# 1.net
KiCad netlist of a schematic drawn in Altium Designer
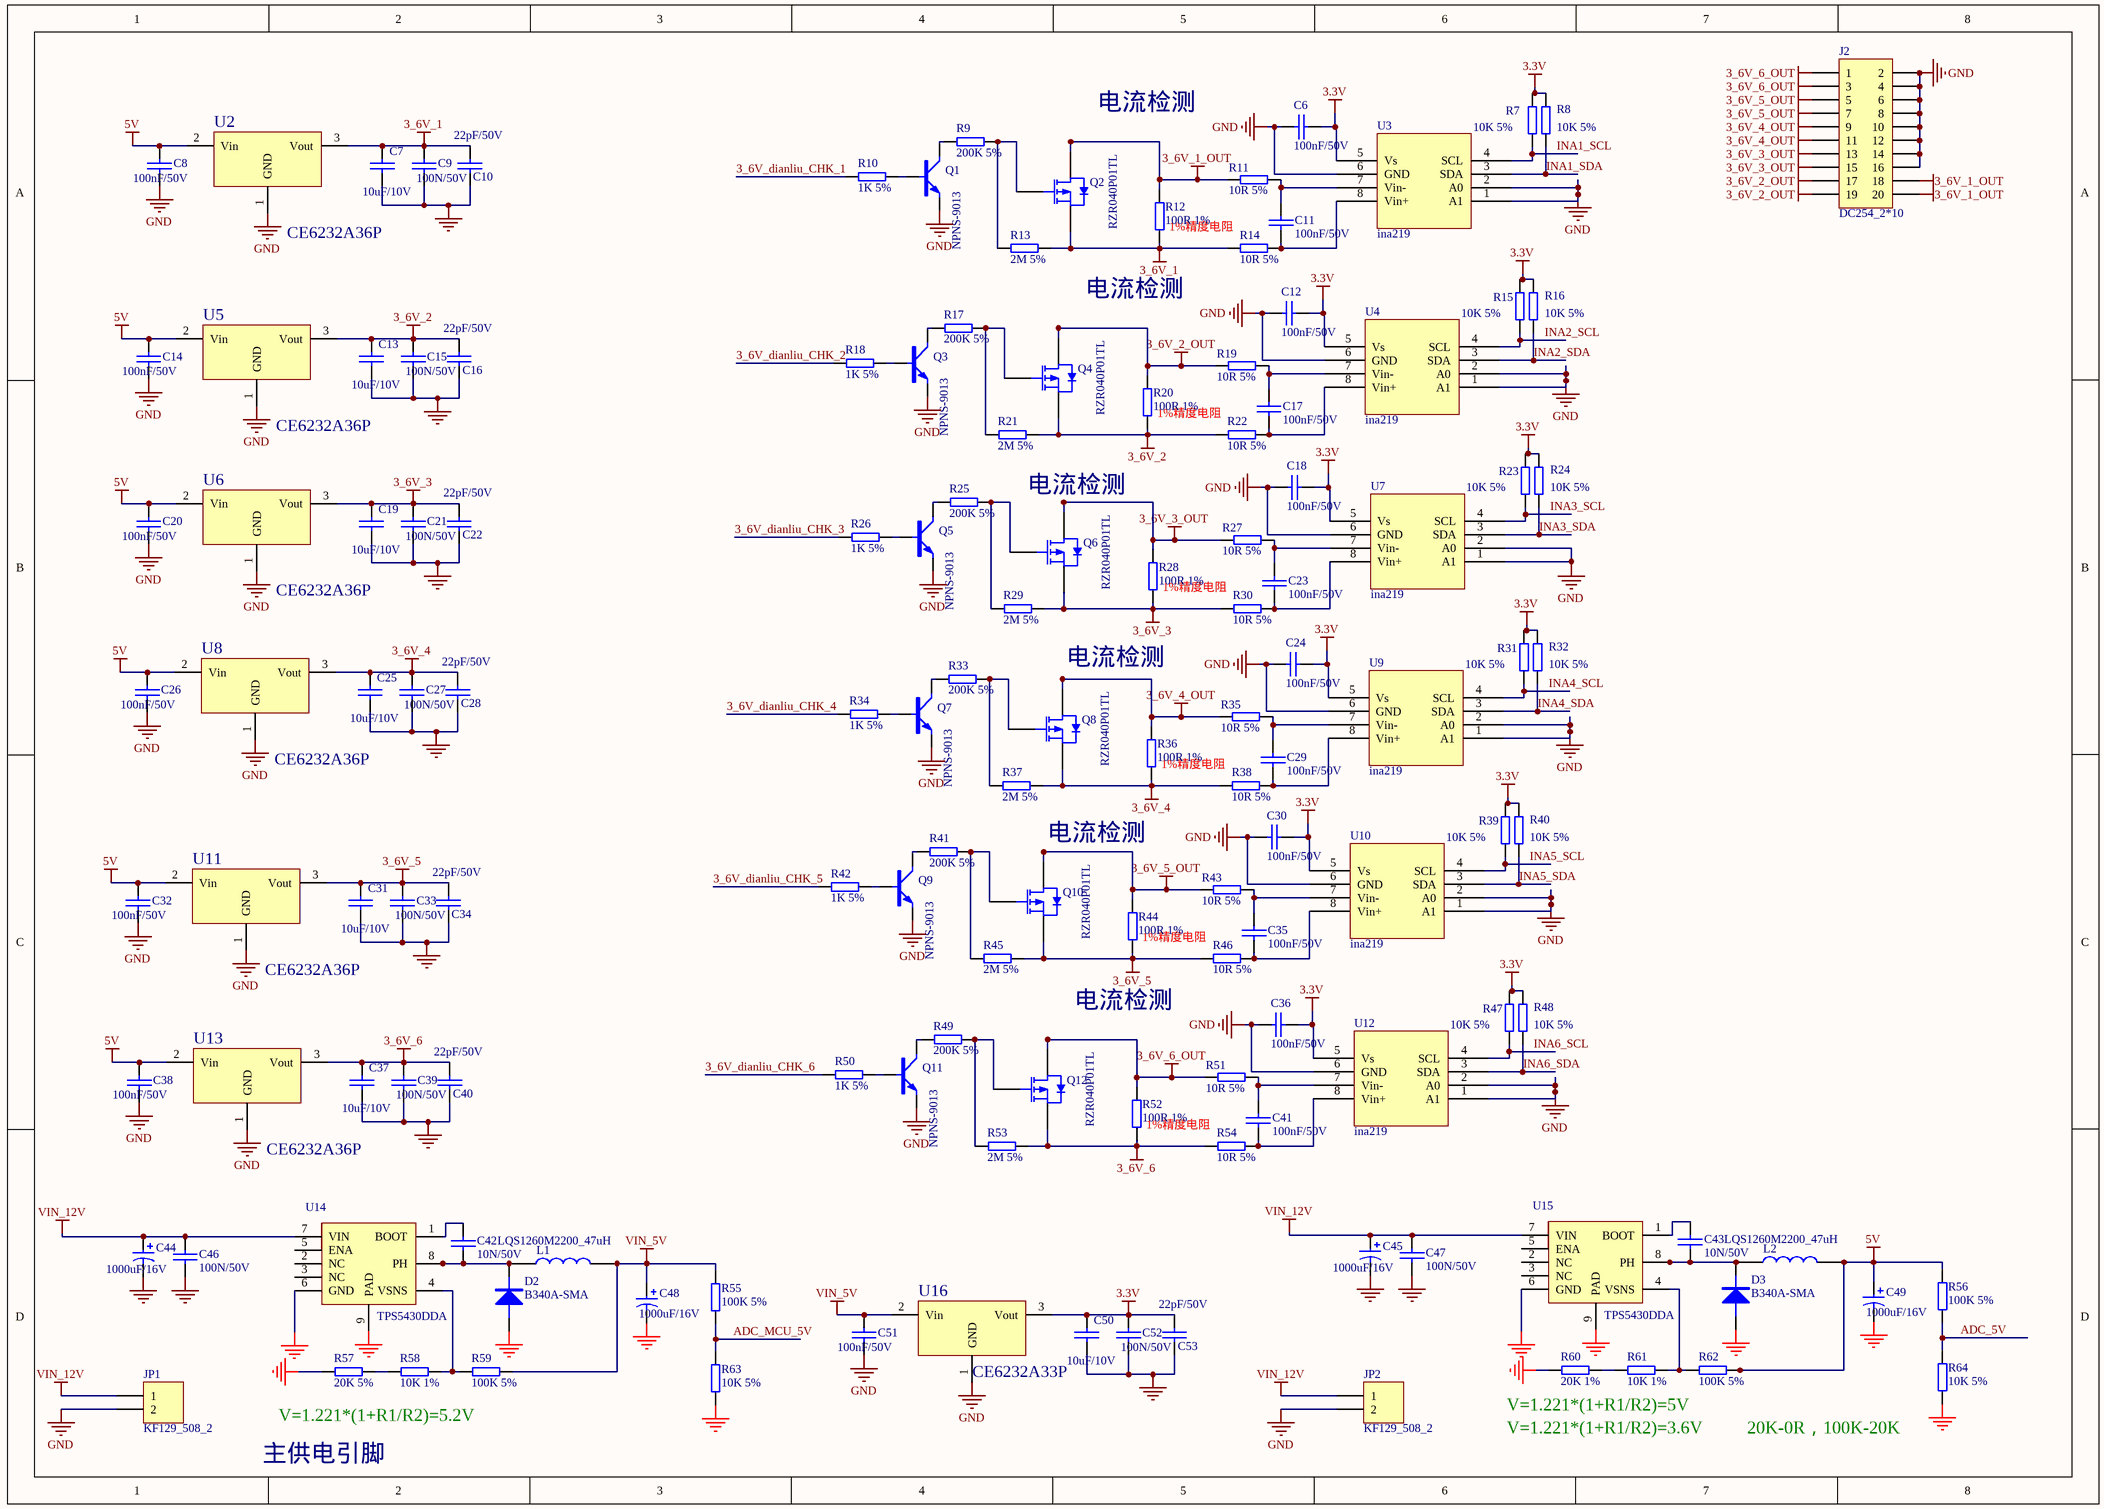
[diagram p0: 功耗测试工装原理图1.SchDoc]

(export (version "E")
  (design (tool "Eeschema 10.0.6"))
  (components
    (comp (ref "C6")
      (value "100nF/50V")
      (footprint "CAP0603")
      (description "104pF,50 V,±10%,0603,国巨,CC0603KRX7R9BB104")
      (fields (field (name "PART NUMBER") "101020103-0021"))
      (libsource (lib "Database_Libs2") (part "CC03K7R9_100N"))
    )
    (comp (ref "C7")
      (value "10uF/10V")
      (footprint "CAP0603")
      (description "106pF,10 V,±10%,0603,村田,GRM188R61A106KE47D")
      (fields (field (name "PART NUMBER") "101020103-0026"))
      (libsource (lib "Database_Libs2") (part "CC03K5R6_10U"))
    )
    (comp (ref "C8")
      (value "100nF/50V")
      (footprint "CAP0603")
      (description "104pF,50 V,±10%,0603,国巨,CC0603KRX7R9BB104")
      (fields (field (name "PART NUMBER") "101020103-0021"))
      (libsource (lib "Database_Libs2") (part "CC03K7R9_100N"))
    )
    (comp (ref "C9")
      (value "100N/50V")
      (footprint "CAP0603")
      (description "100N/50V，±10%，0603")
      (fields (field (name "PART NUMBER") "101020103-0021"))
      (libsource (lib "Database_Libs2") (part "CC03K7R9B_100N"))
    )
    (comp (ref "C10")
      (value "22pF/50V")
      (footprint "CAP0603")
      (description "22pF,50 V,±5%,0603,国巨,CC0603JRNPO9BN22")
      (fields (field (name "PART NUMBER") "101020103-0009"))
      (libsource (lib "Database_Libs2") (part "CC03JPO9_22P"))
    )
    (comp (ref "C11")
      (value "100nF/50V")
      (footprint "CAP0603")
      (description "104pF,50 V,±10%,0603,国巨,CC0603KRX7R9BB104")
      (fields (field (name "PART NUMBER") "101020103-0021"))
      (libsource (lib "Database_Libs2") (part "CC03K7R9_100N"))
    )
    (comp (ref "C12")
      (value "100nF/50V")
      (footprint "CAP0603")
      (description "104pF,50 V,±10%,0603,国巨,CC0603KRX7R9BB104")
      (fields (field (name "PART NUMBER") "101020103-0021"))
      (libsource (lib "Database_Libs2") (part "CC03K7R9_100N"))
    )
    (comp (ref "C13")
      (value "10uF/10V")
      (footprint "CAP0603")
      (description "106pF,10 V,±10%,0603,村田,GRM188R61A106KE47D")
      (fields (field (name "PART NUMBER") "101020103-0026"))
      (libsource (lib "Database_Libs2") (part "CC03K5R6_10U"))
    )
    (comp (ref "C14")
      (value "100nF/50V")
      (footprint "CAP0603")
      (description "104pF,50 V,±10%,0603,国巨,CC0603KRX7R9BB104")
      (fields (field (name "PART NUMBER") "101020103-0021"))
      (libsource (lib "Database_Libs2") (part "CC03K7R9_100N"))
    )
    (comp (ref "C15")
      (value "100N/50V")
      (footprint "CAP0603")
      (description "100N/50V，±10%，0603")
      (fields (field (name "PART NUMBER") "101020103-0021"))
      (libsource (lib "Database_Libs2") (part "CC03K7R9B_100N"))
    )
    (comp (ref "C16")
      (value "22pF/50V")
      (footprint "CAP0603")
      (description "22pF,50 V,±5%,0603,国巨,CC0603JRNPO9BN22")
      (fields (field (name "PART NUMBER") "101020103-0009"))
      (libsource (lib "Database_Libs2") (part "CC03JPO9_22P"))
    )
    (comp (ref "C17")
      (value "100nF/50V")
      (footprint "CAP0603")
      (description "104pF,50 V,±10%,0603,国巨,CC0603KRX7R9BB104")
      (fields (field (name "PART NUMBER") "101020103-0021"))
      (libsource (lib "Database_Libs2") (part "CC03K7R9_100N"))
    )
    (comp (ref "C18")
      (value "100nF/50V")
      (footprint "CAP0603")
      (description "104pF,50 V,±10%,0603,国巨,CC0603KRX7R9BB104")
      (fields (field (name "PART NUMBER") "101020103-0021"))
      (libsource (lib "Database_Libs2") (part "CC03K7R9_100N"))
    )
    (comp (ref "C19")
      (value "10uF/10V")
      (footprint "CAP0603")
      (description "106pF,10 V,±10%,0603,村田,GRM188R61A106KE47D")
      (fields (field (name "PART NUMBER") "101020103-0026"))
      (libsource (lib "Database_Libs2") (part "CC03K5R6_10U"))
    )
    (comp (ref "C20")
      (value "100nF/50V")
      (footprint "CAP0603")
      (description "104pF,50 V,±10%,0603,国巨,CC0603KRX7R9BB104")
      (fields (field (name "PART NUMBER") "101020103-0021"))
      (libsource (lib "Database_Libs2") (part "CC03K7R9_100N"))
    )
    (comp (ref "C21")
      (value "100N/50V")
      (footprint "CAP0603")
      (description "100N/50V，±10%，0603")
      (fields (field (name "PART NUMBER") "101020103-0021"))
      (libsource (lib "Database_Libs2") (part "CC03K7R9B_100N"))
    )
    (comp (ref "C22")
      (value "22pF/50V")
      (footprint "CAP0603")
      (description "22pF,50 V,±5%,0603,国巨,CC0603JRNPO9BN22")
      (fields (field (name "PART NUMBER") "101020103-0009"))
      (libsource (lib "Database_Libs2") (part "CC03JPO9_22P"))
    )
    (comp (ref "C23")
      (value "100nF/50V")
      (footprint "CAP0603")
      (description "104pF,50 V,±10%,0603,国巨,CC0603KRX7R9BB104")
      (fields (field (name "PART NUMBER") "101020103-0021"))
      (libsource (lib "Database_Libs2") (part "CC03K7R9_100N"))
    )
    (comp (ref "C24")
      (value "100nF/50V")
      (footprint "CAP0603")
      (description "104pF,50 V,±10%,0603,国巨,CC0603KRX7R9BB104")
      (fields (field (name "PART NUMBER") "101020103-0021"))
      (libsource (lib "Database_Libs2") (part "CC03K7R9_100N"))
    )
    (comp (ref "C25")
      (value "10uF/10V")
      (footprint "CAP0603")
      (description "106pF,10 V,±10%,0603,村田,GRM188R61A106KE47D")
      (fields (field (name "PART NUMBER") "101020103-0026"))
      (libsource (lib "Database_Libs2") (part "CC03K5R6_10U"))
    )
    (comp (ref "C26")
      (value "100nF/50V")
      (footprint "CAP0603")
      (description "104pF,50 V,±10%,0603,国巨,CC0603KRX7R9BB104")
      (fields (field (name "PART NUMBER") "101020103-0021"))
      (libsource (lib "Database_Libs2") (part "CC03K7R9_100N"))
    )
    (comp (ref "C27")
      (value "100N/50V")
      (footprint "CAP0603")
      (description "100N/50V，±10%，0603")
      (fields (field (name "PART NUMBER") "101020103-0021"))
      (libsource (lib "Database_Libs2") (part "CC03K7R9B_100N"))
    )
    (comp (ref "C28")
      (value "22pF/50V")
      (footprint "CAP0603")
      (description "22pF,50 V,±5%,0603,国巨,CC0603JRNPO9BN22")
      (fields (field (name "PART NUMBER") "101020103-0009"))
      (libsource (lib "Database_Libs2") (part "CC03JPO9_22P"))
    )
    (comp (ref "C29")
      (value "100nF/50V")
      (footprint "CAP0603")
      (description "104pF,50 V,±10%,0603,国巨,CC0603KRX7R9BB104")
      (fields (field (name "PART NUMBER") "101020103-0021"))
      (libsource (lib "Database_Libs2") (part "CC03K7R9_100N"))
    )
    (comp (ref "C30")
      (value "100nF/50V")
      (footprint "CAP0603")
      (description "104pF,50 V,±10%,0603,国巨,CC0603KRX7R9BB104")
      (fields (field (name "PART NUMBER") "101020103-0021"))
      (libsource (lib "Database_Libs2") (part "CC03K7R9_100N"))
    )
    (comp (ref "C31")
      (value "10uF/10V")
      (footprint "CAP0603")
      (description "106pF,10 V,±10%,0603,村田,GRM188R61A106KE47D")
      (fields (field (name "PART NUMBER") "101020103-0026"))
      (libsource (lib "Database_Libs2") (part "CC03K5R6_10U"))
    )
    (comp (ref "C32")
      (value "100nF/50V")
      (footprint "CAP0603")
      (description "104pF,50 V,±10%,0603,国巨,CC0603KRX7R9BB104")
      (fields (field (name "PART NUMBER") "101020103-0021"))
      (libsource (lib "Database_Libs2") (part "CC03K7R9_100N"))
    )
    (comp (ref "C33")
      (value "100N/50V")
      (footprint "CAP0603")
      (description "100N/50V，±10%，0603")
      (fields (field (name "PART NUMBER") "101020103-0021"))
      (libsource (lib "Database_Libs2") (part "CC03K7R9B_100N"))
    )
    (comp (ref "C34")
      (value "22pF/50V")
      (footprint "CAP0603")
      (description "22pF,50 V,±5%,0603,国巨,CC0603JRNPO9BN22")
      (fields (field (name "PART NUMBER") "101020103-0009"))
      (libsource (lib "Database_Libs2") (part "CC03JPO9_22P"))
    )
    (comp (ref "C35")
      (value "100nF/50V")
      (footprint "CAP0603")
      (description "104pF,50 V,±10%,0603,国巨,CC0603KRX7R9BB104")
      (fields (field (name "PART NUMBER") "101020103-0021"))
      (libsource (lib "Database_Libs2") (part "CC03K7R9_100N"))
    )
    (comp (ref "C36")
      (value "100nF/50V")
      (footprint "CAP0603")
      (description "104pF,50 V,±10%,0603,国巨,CC0603KRX7R9BB104")
      (fields (field (name "PART NUMBER") "101020103-0021"))
      (libsource (lib "Database_Libs2") (part "CC03K7R9_100N"))
    )
    (comp (ref "C37")
      (value "10uF/10V")
      (footprint "CAP0603")
      (description "106pF,10 V,±10%,0603,村田,GRM188R61A106KE47D")
      (fields (field (name "PART NUMBER") "101020103-0026"))
      (libsource (lib "Database_Libs2") (part "CC03K5R6_10U"))
    )
    (comp (ref "C38")
      (value "100nF/50V")
      (footprint "CAP0603")
      (description "104pF,50 V,±10%,0603,国巨,CC0603KRX7R9BB104")
      (fields (field (name "PART NUMBER") "101020103-0021"))
      (libsource (lib "Database_Libs2") (part "CC03K7R9_100N"))
    )
    (comp (ref "C39")
      (value "100N/50V")
      (footprint "CAP0603")
      (description "100N/50V，±10%，0603")
      (fields (field (name "PART NUMBER") "101020103-0021"))
      (libsource (lib "Database_Libs2") (part "CC03K7R9B_100N"))
    )
    (comp (ref "C40")
      (value "22pF/50V")
      (footprint "CAP0603")
      (description "22pF,50 V,±5%,0603,国巨,CC0603JRNPO9BN22")
      (fields (field (name "PART NUMBER") "101020103-0009"))
      (libsource (lib "Database_Libs2") (part "CC03JPO9_22P"))
    )
    (comp (ref "C41")
      (value "100nF/50V")
      (footprint "CAP0603")
      (description "104pF,50 V,±10%,0603,国巨,CC0603KRX7R9BB104")
      (fields (field (name "PART NUMBER") "101020103-0021"))
      (libsource (lib "Database_Libs2") (part "CC03K7R9_100N"))
    )
    (comp (ref "C42")
      (value "10N/50V")
      (footprint "CAP0603")
      (description "10N/50V，±10%，0603")
      (fields (field (name "PART NUMBER") "101020103-0007"))
      (libsource (lib "Database_Libs1") (part "CC03K7R9B_10N"))
    )
    (comp (ref "C43")
      (value "10N/50V")
      (footprint "CAP0603")
      (description "10N/50V，±10%，0603")
      (fields (field (name "PART NUMBER") "101020103-0007"))
      (libsource (lib "Database_Libs1") (part "CC03K7R9B_10N"))
    )
    (comp (ref "C44")
      (value "1000uF/16V")
      (footprint "CAPPC_350_800_1600")
      (description "1000uF,16 V,±20%,8*20mm,Rubycon,16ZLH1000M")
      (fields (field (name "PART NUMBER") "1010203-0029"))
      (libsource (lib "Database_Libs2") (part "CAL7MRZLH_1000U_R"))
    )
    (comp (ref "C45")
      (value "1000uF/16V")
      (footprint "CAPPC_350_800_1600")
      (description "1000uF,16 V,±20%,8*20mm,Rubycon,16ZLH1000M")
      (fields (field (name "PART NUMBER") "1010203-0029"))
      (libsource (lib "Database_Libs2") (part "CAL7MRZLH_1000U_R"))
    )
    (comp (ref "C46")
      (value "100N/50V")
      (footprint "CAP0603")
      (description "100N/50V，±10%，0603")
      (fields (field (name "PART NUMBER") "101020103-0021"))
      (libsource (lib "Database_Libs1") (part "CC03K7R9B_100N"))
    )
    (comp (ref "C47")
      (value "100N/50V")
      (footprint "CAP0603")
      (description "100N/50V，±10%，0603")
      (fields (field (name "PART NUMBER") "101020103-0021"))
      (libsource (lib "Database_Libs1") (part "CC03K7R9B_100N"))
    )
    (comp (ref "C48")
      (value "1000uF/16V")
      (footprint "CAPPC_350_800_1600")
      (description "1000uF,16 V,±20%,8*20mm,Rubycon,16ZLH1000M")
      (fields (field (name "PART NUMBER") "1010203-0029"))
      (libsource (lib "Database_Libs2") (part "CAL7MRZLH_1000U_R"))
    )
    (comp (ref "C49")
      (value "1000uF/16V")
      (footprint "CAPPC_350_800_1600")
      (description "1000uF,16 V,±20%,8*20mm,Rubycon,16ZLH1000M")
      (fields (field (name "PART NUMBER") "1010203-0029"))
      (libsource (lib "Database_Libs2") (part "CAL7MRZLH_1000U_R"))
    )
    (comp (ref "C50")
      (value "10uF/10V")
      (footprint "CAP0603")
      (description "106pF,10 V,±10%,0603,村田,GRM188R61A106KE47D")
      (fields (field (name "PART NUMBER") "101020103-0026"))
      (libsource (lib "Database_Libs2") (part "CC03K5R6_10U"))
    )
    (comp (ref "C51")
      (value "100nF/50V")
      (footprint "CAP0603")
      (description "104pF,50 V,±10%,0603,国巨,CC0603KRX7R9BB104")
      (fields (field (name "PART NUMBER") "101020103-0021"))
      (libsource (lib "Database_Libs2") (part "CC03K7R9_100N"))
    )
    (comp (ref "C52")
      (value "100N/50V")
      (footprint "CAP0603")
      (description "100N/50V，±10%，0603")
      (fields (field (name "PART NUMBER") "101020103-0021"))
      (libsource (lib "Database_Libs2") (part "CC03K7R9B_100N"))
    )
    (comp (ref "C53")
      (value "22pF/50V")
      (footprint "CAP0603")
      (description "22pF,50 V,±5%,0603,国巨,CC0603JRNPO9BN22")
      (fields (field (name "PART NUMBER") "101020103-0009"))
      (libsource (lib "Database_Libs2") (part "CC03JPO9_22P"))
    )
    (comp (ref "D2")
      (value "B340A-SMA")
      (footprint "DO-214AC")
      (fields (field (name "PART NUMBER") "101040101-0014"))
      (libsource (lib "Database_Libs1") (part "02_B340A-SMA"))
    )
    (comp (ref "D3")
      (value "B340A-SMA")
      (footprint "DO-214AC")
      (fields (field (name "PART NUMBER") "101040101-0014"))
      (libsource (lib "Database_Libs1") (part "02_B340A-SMA"))
    )
    (comp (ref "J2")
      (value "DC254_2*10")
      (footprint "DC254_2*10")
      (description "DC2 2.54mm 2x10pin,2.54mm间距，2x10pin，32×8.55×27.5mm,母头,双排,双排牛角座")
      (fields (field (name "PART NUMBER") "1010902-0139"))
      (libsource (lib "Database_Libs2") (part "DC254_2*10"))
    )
    (comp (ref "JP1")
      (value "KF129_508_2")
      (footprint "KF129_508_2")
      (description "KF129-2P,螺丝紧固,2,ABS,松涛")
      (fields (field (name "PART NUMBER") "1010904-0015"))
      (libsource (lib "Database_Libs2") (part "KF129_508_2"))
    )
    (comp (ref "JP2")
      (value "KF129_508_2")
      (footprint "KF129_508_2")
      (description "KF129-2P,螺丝紧固,2,ABS,松涛")
      (fields (field (name "PART NUMBER") "1010904-0015"))
      (libsource (lib "Database_Libs2") (part "KF129_508_2"))
    )
    (comp (ref "L1")
      (value "LQS1260M2200_47uH")
      (footprint "LQS1212")
      (description "47uH/2.2A,±20%，0.072Ω，L1200X1200X600")
      (fields (field (name "PART NUMBER") "1010302-0007"))
      (libsource (lib "Database_Libs1") (part "06_LQS1260M2200_47uH"))
    )
    (comp (ref "L2")
      (value "LQS1260M2200_47uH")
      (footprint "LQS1212")
      (description "47uH/2.2A,±20%，0.072Ω，L1200X1200X600")
      (fields (field (name "PART NUMBER") "1010302-0007"))
      (libsource (lib "Database_Libs1") (part "06_LQS1260M2200_47uH"))
    )
    (comp (ref "Q1")
      (value "NPNS-9013")
      (footprint "SOT-23")
      (description "9013,NPN,SOT-23,长电,S9013")
      (fields (field (name "PART NUMBER") "101040201-0002"))
      (libsource (lib "Database_Libs2") (part "03_NPNS-9013"))
    )
    (comp (ref "Q2")
      (value "RZR040P01TL")
      (footprint "SOT-23")
      (description "RZR040P01TL；1.5v导通,P-MOS,SOT-23,罗姆,RZR040P01TL")
      (fields (field (name "PART NUMBER") "101040201-0010"))
      (libsource (lib "Database_Libs2") (part "03_P-RZR040P01TL"))
    )
    (comp (ref "Q3")
      (value "NPNS-9013")
      (footprint "SOT-23")
      (description "9013,NPN,SOT-23,长电,S9013")
      (fields (field (name "PART NUMBER") "101040201-0002"))
      (libsource (lib "Database_Libs2") (part "03_NPNS-9013"))
    )
    (comp (ref "Q4")
      (value "RZR040P01TL")
      (footprint "SOT-23")
      (description "RZR040P01TL；1.5v导通,P-MOS,SOT-23,罗姆,RZR040P01TL")
      (fields (field (name "PART NUMBER") "101040201-0010"))
      (libsource (lib "Database_Libs2") (part "03_P-RZR040P01TL"))
    )
    (comp (ref "Q5")
      (value "NPNS-9013")
      (footprint "SOT-23")
      (description "9013,NPN,SOT-23,长电,S9013")
      (fields (field (name "PART NUMBER") "101040201-0002"))
      (libsource (lib "Database_Libs2") (part "03_NPNS-9013"))
    )
    (comp (ref "Q6")
      (value "RZR040P01TL")
      (footprint "SOT-23")
      (description "RZR040P01TL；1.5v导通,P-MOS,SOT-23,罗姆,RZR040P01TL")
      (fields (field (name "PART NUMBER") "101040201-0010"))
      (libsource (lib "Database_Libs2") (part "03_P-RZR040P01TL"))
    )
    (comp (ref "Q7")
      (value "NPNS-9013")
      (footprint "SOT-23")
      (description "9013,NPN,SOT-23,长电,S9013")
      (fields (field (name "PART NUMBER") "101040201-0002"))
      (libsource (lib "Database_Libs2") (part "03_NPNS-9013"))
    )
    (comp (ref "Q8")
      (value "RZR040P01TL")
      (footprint "SOT-23")
      (description "RZR040P01TL；1.5v导通,P-MOS,SOT-23,罗姆,RZR040P01TL")
      (fields (field (name "PART NUMBER") "101040201-0010"))
      (libsource (lib "Database_Libs2") (part "03_P-RZR040P01TL"))
    )
    (comp (ref "Q9")
      (value "NPNS-9013")
      (footprint "SOT-23")
      (description "9013,NPN,SOT-23,长电,S9013")
      (fields (field (name "PART NUMBER") "101040201-0002"))
      (libsource (lib "Database_Libs2") (part "03_NPNS-9013"))
    )
    (comp (ref "Q10")
      (value "RZR040P01TL")
      (footprint "SOT-23")
      (description "RZR040P01TL；1.5v导通,P-MOS,SOT-23,罗姆,RZR040P01TL")
      (fields (field (name "PART NUMBER") "101040201-0010"))
      (libsource (lib "Database_Libs2") (part "03_P-RZR040P01TL"))
    )
    (comp (ref "Q11")
      (value "NPNS-9013")
      (footprint "SOT-23")
      (description "9013,NPN,SOT-23,长电,S9013")
      (fields (field (name "PART NUMBER") "101040201-0002"))
      (libsource (lib "Database_Libs2") (part "03_NPNS-9013"))
    )
    (comp (ref "Q12")
      (value "RZR040P01TL")
      (footprint "SOT-23")
      (description "RZR040P01TL；1.5v导通,P-MOS,SOT-23,罗姆,RZR040P01TL")
      (fields (field (name "PART NUMBER") "101040201-0010"))
      (libsource (lib "Database_Libs2") (part "03_P-RZR040P01TL"))
    )
    (comp (ref "R7")
      (value "10K 5%")
      (footprint "RES0603")
      (description "国巨,±5%,0603,,155 ℃,-55 ℃,RC0603JR-0710KL,无铅,200 ppm/℃,1/10W,,10K")
      (fields (field (name "PART NUMBER") "101010103-0003"))
      (libsource (lib "Database_Libs2") (part "RC03J_10K"))
    )
    (comp (ref "R8")
      (value "10K 5%")
      (footprint "RES0603")
      (description "国巨,±5%,0603,,155 ℃,-55 ℃,RC0603JR-0710KL,无铅,200 ppm/℃,1/10W,,10K")
      (fields (field (name "PART NUMBER") "101010103-0003"))
      (libsource (lib "Database_Libs2") (part "RC03J_10K"))
    )
    (comp (ref "R9")
      (value "200K 5%")
      (footprint "RES0603")
      (description "200K,±5%,1/10W,0603,国巨,RC0603JR-07200KL")
      (fields (field (name "PART NUMBER") "101010103-0034"))
      (libsource (lib "Database_Libs2") (part "RC03J_200K"))
    )
    (comp (ref "R10")
      (value "1K 5%")
      (footprint "RES0603")
      (description "1K,±5%,1/10W,0603,国巨,RC0603JR-071KL")
      (fields (field (name "PART NUMBER") "101010103-0008"))
      (libsource (lib "Database_Libs2") (part "RC03J_1K"))
    )
    (comp (ref "R11")
      (value "10R 5%")
      (footprint "RES0603")
      (description "10R,±5%,1/10W,0603,国巨,RC0603JR-0710RL")
      (fields (field (name "PART NUMBER") "101010103-0017"))
      (libsource (lib "Database_Libs2") (part "RC03J_10R"))
    )
    (comp (ref "R12")
      (value "100R 1%")
      (footprint "RES0603")
      (description "100Ω,±1%,1/10W,0603,国巨股份有限公司,RC0603FR-07100RL")
      (fields (field (name "PART NUMBER") "101010103-0041"))
      (libsource (lib "Database_Libs2") (part "RC03J_100R"))
    )
    (comp (ref "R13")
      (value "2M 5%")
      (footprint "RES0603")
      (description "国巨,±5%,0603,,155 ℃,-55 ℃,RC0603JR-072ML,含铅,100 ppm/℃,1/10W,,2M")
      (fields (field (name "PART NUMBER") "101010103-0025"))
      (libsource (lib "Database_Libs2") (part "RC03J_2M"))
    )
    (comp (ref "R14")
      (value "10R 5%")
      (footprint "RES0603")
      (description "10R,±5%,1/10W,0603,国巨,RC0603JR-0710RL")
      (fields (field (name "PART NUMBER") "101010103-0017"))
      (libsource (lib "Database_Libs2") (part "RC03J_10R"))
    )
    (comp (ref "R15")
      (value "10K 5%")
      (footprint "RES0603")
      (description "国巨,±5%,0603,,155 ℃,-55 ℃,RC0603JR-0710KL,无铅,200 ppm/℃,1/10W,,10K")
      (fields (field (name "PART NUMBER") "101010103-0003"))
      (libsource (lib "Database_Libs2") (part "RC03J_10K"))
    )
    (comp (ref "R16")
      (value "10K 5%")
      (footprint "RES0603")
      (description "国巨,±5%,0603,,155 ℃,-55 ℃,RC0603JR-0710KL,无铅,200 ppm/℃,1/10W,,10K")
      (fields (field (name "PART NUMBER") "101010103-0003"))
      (libsource (lib "Database_Libs2") (part "RC03J_10K"))
    )
    (comp (ref "R17")
      (value "200K 5%")
      (footprint "RES0603")
      (description "200K,±5%,1/10W,0603,国巨,RC0603JR-07200KL")
      (fields (field (name "PART NUMBER") "101010103-0034"))
      (libsource (lib "Database_Libs2") (part "RC03J_200K"))
    )
    (comp (ref "R18")
      (value "1K 5%")
      (footprint "RES0603")
      (description "1K,±5%,1/10W,0603,国巨,RC0603JR-071KL")
      (fields (field (name "PART NUMBER") "101010103-0008"))
      (libsource (lib "Database_Libs2") (part "RC03J_1K"))
    )
    (comp (ref "R19")
      (value "10R 5%")
      (footprint "RES0603")
      (description "10R,±5%,1/10W,0603,国巨,RC0603JR-0710RL")
      (fields (field (name "PART NUMBER") "101010103-0017"))
      (libsource (lib "Database_Libs2") (part "RC03J_10R"))
    )
    (comp (ref "R20")
      (value "100R 1%")
      (footprint "RES0603")
      (description "100Ω,±1%,1/10W,0603,国巨股份有限公司,RC0603FR-07100RL")
      (fields (field (name "PART NUMBER") "101010103-0041"))
      (libsource (lib "Database_Libs2") (part "RC03J_100R"))
    )
    (comp (ref "R21")
      (value "2M 5%")
      (footprint "RES0603")
      (description "国巨,±5%,0603,,155 ℃,-55 ℃,RC0603JR-072ML,含铅,100 ppm/℃,1/10W,,2M")
      (fields (field (name "PART NUMBER") "101010103-0025"))
      (libsource (lib "Database_Libs2") (part "RC03J_2M"))
    )
    (comp (ref "R22")
      (value "10R 5%")
      (footprint "RES0603")
      (description "10R,±5%,1/10W,0603,国巨,RC0603JR-0710RL")
      (fields (field (name "PART NUMBER") "101010103-0017"))
      (libsource (lib "Database_Libs2") (part "RC03J_10R"))
    )
    (comp (ref "R23")
      (value "10K 5%")
      (footprint "RES0603")
      (description "国巨,±5%,0603,,155 ℃,-55 ℃,RC0603JR-0710KL,无铅,200 ppm/℃,1/10W,,10K")
      (fields (field (name "PART NUMBER") "101010103-0003"))
      (libsource (lib "Database_Libs2") (part "RC03J_10K"))
    )
    (comp (ref "R24")
      (value "10K 5%")
      (footprint "RES0603")
      (description "国巨,±5%,0603,,155 ℃,-55 ℃,RC0603JR-0710KL,无铅,200 ppm/℃,1/10W,,10K")
      (fields (field (name "PART NUMBER") "101010103-0003"))
      (libsource (lib "Database_Libs2") (part "RC03J_10K"))
    )
    (comp (ref "R25")
      (value "200K 5%")
      (footprint "RES0603")
      (description "200K,±5%,1/10W,0603,国巨,RC0603JR-07200KL")
      (fields (field (name "PART NUMBER") "101010103-0034"))
      (libsource (lib "Database_Libs2") (part "RC03J_200K"))
    )
    (comp (ref "R26")
      (value "1K 5%")
      (footprint "RES0603")
      (description "1K,±5%,1/10W,0603,国巨,RC0603JR-071KL")
      (fields (field (name "PART NUMBER") "101010103-0008"))
      (libsource (lib "Database_Libs2") (part "RC03J_1K"))
    )
    (comp (ref "R27")
      (value "10R 5%")
      (footprint "RES0603")
      (description "10R,±5%,1/10W,0603,国巨,RC0603JR-0710RL")
      (fields (field (name "PART NUMBER") "101010103-0017"))
      (libsource (lib "Database_Libs2") (part "RC03J_10R"))
    )
    (comp (ref "R28")
      (value "100R 1%")
      (footprint "RES0603")
      (description "100Ω,±1%,1/10W,0603,国巨股份有限公司,RC0603FR-07100RL")
      (fields (field (name "PART NUMBER") "101010103-0041"))
      (libsource (lib "Database_Libs2") (part "RC03J_100R"))
    )
    (comp (ref "R29")
      (value "2M 5%")
      (footprint "RES0603")
      (description "国巨,±5%,0603,,155 ℃,-55 ℃,RC0603JR-072ML,含铅,100 ppm/℃,1/10W,,2M")
      (fields (field (name "PART NUMBER") "101010103-0025"))
      (libsource (lib "Database_Libs2") (part "RC03J_2M"))
    )
    (comp (ref "R30")
      (value "10R 5%")
      (footprint "RES0603")
      (description "10R,±5%,1/10W,0603,国巨,RC0603JR-0710RL")
      (fields (field (name "PART NUMBER") "101010103-0017"))
      (libsource (lib "Database_Libs2") (part "RC03J_10R"))
    )
    (comp (ref "R31")
      (value "10K 5%")
      (footprint "RES0603")
      (description "国巨,±5%,0603,,155 ℃,-55 ℃,RC0603JR-0710KL,无铅,200 ppm/℃,1/10W,,10K")
      (fields (field (name "PART NUMBER") "101010103-0003"))
      (libsource (lib "Database_Libs2") (part "RC03J_10K"))
    )
    (comp (ref "R32")
      (value "10K 5%")
      (footprint "RES0603")
      (description "国巨,±5%,0603,,155 ℃,-55 ℃,RC0603JR-0710KL,无铅,200 ppm/℃,1/10W,,10K")
      (fields (field (name "PART NUMBER") "101010103-0003"))
      (libsource (lib "Database_Libs2") (part "RC03J_10K"))
    )
    (comp (ref "R33")
      (value "200K 5%")
      (footprint "RES0603")
      (description "200K,±5%,1/10W,0603,国巨,RC0603JR-07200KL")
      (fields (field (name "PART NUMBER") "101010103-0034"))
      (libsource (lib "Database_Libs2") (part "RC03J_200K"))
    )
    (comp (ref "R34")
      (value "1K 5%")
      (footprint "RES0603")
      (description "1K,±5%,1/10W,0603,国巨,RC0603JR-071KL")
      (fields (field (name "PART NUMBER") "101010103-0008"))
      (libsource (lib "Database_Libs2") (part "RC03J_1K"))
    )
    (comp (ref "R35")
      (value "10R 5%")
      (footprint "RES0603")
      (description "10R,±5%,1/10W,0603,国巨,RC0603JR-0710RL")
      (fields (field (name "PART NUMBER") "101010103-0017"))
      (libsource (lib "Database_Libs2") (part "RC03J_10R"))
    )
    (comp (ref "R36")
      (value "100R 1%")
      (footprint "RES0603")
      (description "100Ω,±1%,1/10W,0603,国巨股份有限公司,RC0603FR-07100RL")
      (fields (field (name "PART NUMBER") "101010103-0041"))
      (libsource (lib "Database_Libs2") (part "RC03J_100R"))
    )
    (comp (ref "R37")
      (value "2M 5%")
      (footprint "RES0603")
      (description "国巨,±5%,0603,,155 ℃,-55 ℃,RC0603JR-072ML,含铅,100 ppm/℃,1/10W,,2M")
      (fields (field (name "PART NUMBER") "101010103-0025"))
      (libsource (lib "Database_Libs2") (part "RC03J_2M"))
    )
    (comp (ref "R38")
      (value "10R 5%")
      (footprint "RES0603")
      (description "10R,±5%,1/10W,0603,国巨,RC0603JR-0710RL")
      (fields (field (name "PART NUMBER") "101010103-0017"))
      (libsource (lib "Database_Libs2") (part "RC03J_10R"))
    )
    (comp (ref "R39")
      (value "10K 5%")
      (footprint "RES0603")
      (description "国巨,±5%,0603,,155 ℃,-55 ℃,RC0603JR-0710KL,无铅,200 ppm/℃,1/10W,,10K")
      (fields (field (name "PART NUMBER") "101010103-0003"))
      (libsource (lib "Database_Libs2") (part "RC03J_10K"))
    )
    (comp (ref "R40")
      (value "10K 5%")
      (footprint "RES0603")
      (description "国巨,±5%,0603,,155 ℃,-55 ℃,RC0603JR-0710KL,无铅,200 ppm/℃,1/10W,,10K")
      (fields (field (name "PART NUMBER") "101010103-0003"))
      (libsource (lib "Database_Libs2") (part "RC03J_10K"))
    )
    (comp (ref "R41")
      (value "200K 5%")
      (footprint "RES0603")
      (description "200K,±5%,1/10W,0603,国巨,RC0603JR-07200KL")
      (fields (field (name "PART NUMBER") "101010103-0034"))
      (libsource (lib "Database_Libs2") (part "RC03J_200K"))
    )
    (comp (ref "R42")
      (value "1K 5%")
      (footprint "RES0603")
      (description "1K,±5%,1/10W,0603,国巨,RC0603JR-071KL")
      (fields (field (name "PART NUMBER") "101010103-0008"))
      (libsource (lib "Database_Libs2") (part "RC03J_1K"))
    )
    (comp (ref "R43")
      (value "10R 5%")
      (footprint "RES0603")
      (description "10R,±5%,1/10W,0603,国巨,RC0603JR-0710RL")
      (fields (field (name "PART NUMBER") "101010103-0017"))
      (libsource (lib "Database_Libs2") (part "RC03J_10R"))
    )
    (comp (ref "R44")
      (value "100R 1%")
      (footprint "RES0603")
      (description "100Ω,±1%,1/10W,0603,国巨股份有限公司,RC0603FR-07100RL")
      (fields (field (name "PART NUMBER") "101010103-0041"))
      (libsource (lib "Database_Libs2") (part "RC03J_100R"))
    )
    (comp (ref "R45")
      (value "2M 5%")
      (footprint "RES0603")
      (description "国巨,±5%,0603,,155 ℃,-55 ℃,RC0603JR-072ML,含铅,100 ppm/℃,1/10W,,2M")
      (fields (field (name "PART NUMBER") "101010103-0025"))
      (libsource (lib "Database_Libs2") (part "RC03J_2M"))
    )
    (comp (ref "R46")
      (value "10R 5%")
      (footprint "RES0603")
      (description "10R,±5%,1/10W,0603,国巨,RC0603JR-0710RL")
      (fields (field (name "PART NUMBER") "101010103-0017"))
      (libsource (lib "Database_Libs2") (part "RC03J_10R"))
    )
    (comp (ref "R47")
      (value "10K 5%")
      (footprint "RES0603")
      (description "国巨,±5%,0603,,155 ℃,-55 ℃,RC0603JR-0710KL,无铅,200 ppm/℃,1/10W,,10K")
      (fields (field (name "PART NUMBER") "101010103-0003"))
      (libsource (lib "Database_Libs2") (part "RC03J_10K"))
    )
    (comp (ref "R48")
      (value "10K 5%")
      (footprint "RES0603")
      (description "国巨,±5%,0603,,155 ℃,-55 ℃,RC0603JR-0710KL,无铅,200 ppm/℃,1/10W,,10K")
      (fields (field (name "PART NUMBER") "101010103-0003"))
      (libsource (lib "Database_Libs2") (part "RC03J_10K"))
    )
    (comp (ref "R49")
      (value "200K 5%")
      (footprint "RES0603")
      (description "200K,±5%,1/10W,0603,国巨,RC0603JR-07200KL")
      (fields (field (name "PART NUMBER") "101010103-0034"))
      (libsource (lib "Database_Libs2") (part "RC03J_200K"))
    )
    (comp (ref "R50")
      (value "1K 5%")
      (footprint "RES0603")
      (description "1K,±5%,1/10W,0603,国巨,RC0603JR-071KL")
      (fields (field (name "PART NUMBER") "101010103-0008"))
      (libsource (lib "Database_Libs2") (part "RC03J_1K"))
    )
    (comp (ref "R51")
      (value "10R 5%")
      (footprint "RES0603")
      (description "10R,±5%,1/10W,0603,国巨,RC0603JR-0710RL")
      (fields (field (name "PART NUMBER") "101010103-0017"))
      (libsource (lib "Database_Libs2") (part "RC03J_10R"))
    )
    (comp (ref "R52")
      (value "100R 1%")
      (footprint "RES0603")
      (description "100Ω,±1%,1/10W,0603,国巨股份有限公司,RC0603FR-07100RL")
      (fields (field (name "PART NUMBER") "101010103-0041"))
      (libsource (lib "Database_Libs2") (part "RC03J_100R"))
    )
    (comp (ref "R53")
      (value "2M 5%")
      (footprint "RES0603")
      (description "国巨,±5%,0603,,155 ℃,-55 ℃,RC0603JR-072ML,含铅,100 ppm/℃,1/10W,,2M")
      (fields (field (name "PART NUMBER") "101010103-0025"))
      (libsource (lib "Database_Libs2") (part "RC03J_2M"))
    )
    (comp (ref "R54")
      (value "10R 5%")
      (footprint "RES0603")
      (description "10R,±5%,1/10W,0603,国巨,RC0603JR-0710RL")
      (fields (field (name "PART NUMBER") "101010103-0017"))
      (libsource (lib "Database_Libs2") (part "RC03J_10R"))
    )
    (comp (ref "R55")
      (value "100K 5%")
      (footprint "RES0603")
      (description "100K±5%,1/10W,0603")
      (fields (field (name "PART NUMBER") "101010103-0005"))
      (libsource (lib "Database_Libs1") (part "RC03JF_100K"))
    )
    (comp (ref "R56")
      (value "100K 5%")
      (footprint "RES0603")
      (description "100K±5%,1/10W,0603")
      (fields (field (name "PART NUMBER") "101010103-0005"))
      (libsource (lib "Database_Libs1") (part "RC03JF_100K"))
    )
    (comp (ref "R57")
      (value "20K 5%")
      (footprint "RES0603")
      (description "国巨,±5%,0603,,155 ℃,-55 ℃,RC0603JR-0720KL,无铅,200 ppm/℃,1/10W,,20K")
      (fields (field (name "PART NUMBER") "101010103-0004"))
      (libsource (lib "Database_Libs2") (part "RC03J_20K"))
    )
    (comp (ref "R58")
      (value "10K 1%")
      (footprint "RES0603")
      (description "8.2k±1%,1/10W,0603")
      (fields (field (name "PART NUMBER") "101010103-0053"))
      (libsource (lib "Database_Libs1") (part "RC03FF_8.2K"))
    )
    (comp (ref "R59")
      (value "100K 5%")
      (footprint "RES0603")
      (description "国巨,±5%,0603,,155 ℃,-55 ℃,RC0603JR-07100KL,无铅,100 ppm/℃,1/10W,,100K")
      (fields (field (name "PART NUMBER") "101010103-0005"))
      (libsource (lib "Database_Libs2") (part "RC03J_100K"))
    )
    (comp (ref "R60")
      (value "20K 1%")
      (footprint "RES0603")
      (description "20K,±1%,1/10W,0603,国巨,RC0603FR-0720KL")
      (fields (field (name "PART NUMBER") "101010103-0048"))
      (libsource (lib "Database_Libs2") (part "RC03J_20K"))
    )
    (comp (ref "R61")
      (value "10K 1%")
      (footprint "RES0603")
      (description "8.2k±1%,1/10W,0603")
      (fields (field (name "PART NUMBER") "101010103-0053"))
      (libsource (lib "Database_Libs1") (part "RC03FF_8.2K"))
    )
    (comp (ref "R62")
      (value "100K 5%")
      (footprint "RES0603")
      (description "国巨,±5%,0603,,155 ℃,-55 ℃,RC0603JR-07100KL,无铅,100 ppm/℃,1/10W,,100K")
      (fields (field (name "PART NUMBER") "101010103-0005"))
      (libsource (lib "Database_Libs2") (part "RC03J_100K"))
    )
    (comp (ref "R63")
      (value "10K 5%")
      (footprint "RES0603")
      (description "100K±5%,1/10W,0603")
      (fields (field (name "PART NUMBER") "101010103-0005"))
      (libsource (lib "Database_Libs1") (part "RC03JF_100K"))
    )
    (comp (ref "R64")
      (value "10K 5%")
      (footprint "RES0603")
      (description "100K±5%,1/10W,0603")
      (fields (field (name "PART NUMBER") "101010103-0005"))
      (libsource (lib "Database_Libs1") (part "RC03JF_100K"))
    )
    (comp (ref "U2")
      (value "CE6232A36P")
      (footprint "SOT-89")
      (description "CE6232A36P,CE6232A36P,SOT89-3,8 V,1.8 V,0.11 V,3.6 V,600mA,0.8 uA,南京芯力微电子有限公司")
      (fields (field (name "PART NUMBER") "1010503-0031"))
      (libsource (lib "Database_Libs2") (part "02_CE6232A36P"))
    )
    (comp (ref "U3") (value "ina219") (footprint "SO-8") (libsource (lib "Schlib1") (part "Component_2")))
    (comp (ref "U4") (value "ina219") (footprint "SO-8") (libsource (lib "Schlib1") (part "Component_2")))
    (comp (ref "U5")
      (value "CE6232A36P")
      (footprint "SOT-89")
      (description "CE6232A36P,CE6232A36P,SOT89-3,8 V,1.8 V,0.11 V,3.6 V,600mA,0.8 uA,南京芯力微电子有限公司")
      (fields (field (name "PART NUMBER") "1010503-0031"))
      (libsource (lib "Database_Libs2") (part "02_CE6232A36P"))
    )
    (comp (ref "U6")
      (value "CE6232A36P")
      (footprint "SOT-89")
      (description "CE6232A36P,CE6232A36P,SOT89-3,8 V,1.8 V,0.11 V,3.6 V,600mA,0.8 uA,南京芯力微电子有限公司")
      (fields (field (name "PART NUMBER") "1010503-0031"))
      (libsource (lib "Database_Libs2") (part "02_CE6232A36P"))
    )
    (comp (ref "U7") (value "ina219") (footprint "SO-8") (libsource (lib "Schlib1") (part "Component_2")))
    (comp (ref "U8")
      (value "CE6232A36P")
      (footprint "SOT-89")
      (description "CE6232A36P,CE6232A36P,SOT89-3,8 V,1.8 V,0.11 V,3.6 V,600mA,0.8 uA,南京芯力微电子有限公司")
      (fields (field (name "PART NUMBER") "1010503-0031"))
      (libsource (lib "Database_Libs2") (part "02_CE6232A36P"))
    )
    (comp (ref "U9") (value "ina219") (footprint "SO-8") (libsource (lib "Schlib1") (part "Component_2")))
    (comp (ref "U10") (value "ina219") (footprint "SO-8") (libsource (lib "Schlib1") (part "Component_2")))
    (comp (ref "U11")
      (value "CE6232A36P")
      (footprint "SOT-89")
      (description "CE6232A36P,CE6232A36P,SOT89-3,8 V,1.8 V,0.11 V,3.6 V,600mA,0.8 uA,南京芯力微电子有限公司")
      (fields (field (name "PART NUMBER") "1010503-0031"))
      (libsource (lib "Database_Libs2") (part "02_CE6232A36P"))
    )
    (comp (ref "U12") (value "ina219") (footprint "SO-8") (libsource (lib "Schlib1") (part "Component_2")))
    (comp (ref "U13")
      (value "CE6232A36P")
      (footprint "SOT-89")
      (description "CE6232A36P,CE6232A36P,SOT89-3,8 V,1.8 V,0.11 V,3.6 V,600mA,0.8 uA,南京芯力微电子有限公司")
      (fields (field (name "PART NUMBER") "1010503-0031"))
      (libsource (lib "Database_Libs2") (part "02_CE6232A36P"))
    )
    (comp (ref "U14")
      (value "TPS5430DDA")
      (footprint "SOP-8-P")
      (description "TPS5430DDA,SOP8,TI,TPS5430DDA")
      (fields (field (name "PART NUMBER") "101050101-0053"))
      (libsource (lib "Database_Libs2") (part "02_TPS5430DDA"))
    )
    (comp (ref "U15")
      (value "TPS5430DDA")
      (footprint "SOP-8-P")
      (description "TPS5430DDA,SOP8,TI,TPS5430DDA")
      (fields (field (name "PART NUMBER") "101050101-0053"))
      (libsource (lib "Database_Libs2") (part "02_TPS5430DDA"))
    )
    (comp (ref "U16")
      (value "CE6232A33P")
      (footprint "SOT-89")
      (description "CE6232-3.3,CE6232-3.3,SOT89-3,8V,1.8V,0.11V,3.3V,300mA,0.8uA,南京芯力微电子有限公司")
      (fields (field (name "PART NUMBER") "1010503-0029"))
      (libsource (lib "Database_Libs2") (part "02_CE6232A33P"))
    )
  )
  (nets
    (net (code "1") (name "/3_6V_dianliu_CHK_1") (class "Default")
      (node (ref "R10") (pin "2") (pinfunction "2_2") (pintype "passive"))
    )
    (net (code "2") (name "/3_6V_dianliu_CHK_2") (class "Default")
      (node (ref "R18") (pin "2") (pinfunction "2_2") (pintype "passive"))
    )
    (net (code "3") (name "/3_6V_dianliu_CHK_3") (class "Default")
      (node (ref "R26") (pin "2") (pinfunction "2_2") (pintype "passive"))
    )
    (net (code "4") (name "/3_6V_dianliu_CHK_4") (class "Default")
      (node (ref "R34") (pin "2") (pinfunction "2_2") (pintype "passive"))
    )
    (net (code "5") (name "/3_6V_dianliu_CHK_5") (class "Default")
      (node (ref "R42") (pin "2") (pinfunction "2_2") (pintype "passive"))
    )
    (net (code "6") (name "/3_6V_dianliu_CHK_6") (class "Default")
      (node (ref "R50") (pin "2") (pinfunction "2_2") (pintype "passive"))
    )
    (net (code "7") (name "/ADC_5V") (class "Default")
      (node (ref "R56") (pin "1") (pinfunction "1_1") (pintype "passive"))
      (node (ref "R64") (pin "2") (pinfunction "2_2") (pintype "passive"))
    )
    (net (code "8") (name "/ADC_MCU_5V") (class "Default")
      (node (ref "R55") (pin "1") (pinfunction "1_1") (pintype "passive"))
      (node (ref "R63") (pin "2") (pinfunction "2_2") (pintype "passive"))
    )
    (net (code "9") (name "/INA1_SCL") (class "Default")
      (node (ref "R7") (pin "2") (pinfunction "2_2") (pintype "passive"))
      (node (ref "U3") (pin "4") (pinfunction "SCL_4") (pintype "passive"))
    )
    (net (code "10") (name "/INA1_SDA") (class "Default")
      (node (ref "R8") (pin "2") (pinfunction "2_2") (pintype "passive"))
      (node (ref "U3") (pin "3") (pinfunction "SDA_3") (pintype "passive"))
    )
    (net (code "11") (name "/INA2_SCL") (class "Default")
      (node (ref "R15") (pin "2") (pinfunction "2_2") (pintype "passive"))
      (node (ref "U4") (pin "4") (pinfunction "SCL_4") (pintype "passive"))
    )
    (net (code "12") (name "/INA2_SDA") (class "Default")
      (node (ref "R16") (pin "2") (pinfunction "2_2") (pintype "passive"))
      (node (ref "U4") (pin "3") (pinfunction "SDA_3") (pintype "passive"))
    )
    (net (code "13") (name "/INA3_SCL") (class "Default")
      (node (ref "R23") (pin "2") (pinfunction "2_2") (pintype "passive"))
      (node (ref "U7") (pin "4") (pinfunction "SCL_4") (pintype "passive"))
    )
    (net (code "14") (name "/INA3_SDA") (class "Default")
      (node (ref "R24") (pin "2") (pinfunction "2_2") (pintype "passive"))
      (node (ref "U7") (pin "3") (pinfunction "SDA_3") (pintype "passive"))
    )
    (net (code "15") (name "/INA4_SCL") (class "Default")
      (node (ref "R31") (pin "2") (pinfunction "2_2") (pintype "passive"))
      (node (ref "U9") (pin "4") (pinfunction "SCL_4") (pintype "passive"))
    )
    (net (code "16") (name "/INA4_SDA") (class "Default")
      (node (ref "R32") (pin "2") (pinfunction "2_2") (pintype "passive"))
      (node (ref "U9") (pin "3") (pinfunction "SDA_3") (pintype "passive"))
    )
    (net (code "17") (name "/INA5_SCL") (class "Default")
      (node (ref "R39") (pin "2") (pinfunction "2_2") (pintype "passive"))
      (node (ref "U10") (pin "4") (pinfunction "SCL_4") (pintype "passive"))
    )
    (net (code "18") (name "/INA5_SDA") (class "Default")
      (node (ref "R40") (pin "2") (pinfunction "2_2") (pintype "passive"))
      (node (ref "U10") (pin "3") (pinfunction "SDA_3") (pintype "passive"))
    )
    (net (code "19") (name "/INA6_SCL") (class "Default")
      (node (ref "R47") (pin "2") (pinfunction "2_2") (pintype "passive"))
      (node (ref "U12") (pin "4") (pinfunction "SCL_4") (pintype "passive"))
    )
    (net (code "20") (name "/INA6_SDA") (class "Default")
      (node (ref "R48") (pin "2") (pinfunction "2_2") (pintype "passive"))
      (node (ref "U12") (pin "3") (pinfunction "SDA_3") (pintype "passive"))
    )
    (net (code "21") (name "3.3V") (class "Default")
      (node (ref "C12") (pin "2") (pinfunction "2_2") (pintype "passive"))
      (node (ref "C18") (pin "2") (pinfunction "2_2") (pintype "passive"))
      (node (ref "C24") (pin "2") (pinfunction "2_2") (pintype "passive"))
      (node (ref "C30") (pin "2") (pinfunction "2_2") (pintype "passive"))
      (node (ref "C36") (pin "2") (pinfunction "2_2") (pintype "passive"))
      (node (ref "C50") (pin "1") (pinfunction "1_1") (pintype "passive"))
      (node (ref "C52") (pin "1") (pinfunction "1_1") (pintype "passive"))
      (node (ref "C53") (pin "1") (pinfunction "1_1") (pintype "passive"))
      (node (ref "C6") (pin "2") (pinfunction "2_2") (pintype "passive"))
      (node (ref "R15") (pin "1") (pinfunction "1_1") (pintype "passive"))
      (node (ref "R16") (pin "1") (pinfunction "1_1") (pintype "passive"))
      (node (ref "R23") (pin "1") (pinfunction "1_1") (pintype "passive"))
      (node (ref "R24") (pin "1") (pinfunction "1_1") (pintype "passive"))
      (node (ref "R31") (pin "1") (pinfunction "1_1") (pintype "passive"))
      (node (ref "R32") (pin "1") (pinfunction "1_1") (pintype "passive"))
      (node (ref "R39") (pin "1") (pinfunction "1_1") (pintype "passive"))
      (node (ref "R40") (pin "1") (pinfunction "1_1") (pintype "passive"))
      (node (ref "R47") (pin "1") (pinfunction "1_1") (pintype "passive"))
      (node (ref "R48") (pin "1") (pinfunction "1_1") (pintype "passive"))
      (node (ref "R7") (pin "1") (pinfunction "1_1") (pintype "passive"))
      (node (ref "R8") (pin "1") (pinfunction "1_1") (pintype "passive"))
      (node (ref "U10") (pin "5") (pinfunction "Vs_5") (pintype "passive"))
      (node (ref "U12") (pin "5") (pinfunction "Vs_5") (pintype "passive"))
      (node (ref "U16") (pin "3") (pinfunction "Vout_3") (pintype "passive"))
      (node (ref "U3") (pin "5") (pinfunction "Vs_5") (pintype "passive"))
      (node (ref "U4") (pin "5") (pinfunction "Vs_5") (pintype "passive"))
      (node (ref "U7") (pin "5") (pinfunction "Vs_5") (pintype "passive"))
      (node (ref "U9") (pin "5") (pinfunction "Vs_5") (pintype "passive"))
    )
    (net (code "22") (name "3_6V_1") (class "Default")
      (node (ref "C10") (pin "1") (pinfunction "1_1") (pintype "passive"))
      (node (ref "C7") (pin "1") (pinfunction "1_1") (pintype "passive"))
      (node (ref "C9") (pin "1") (pinfunction "1_1") (pintype "passive"))
      (node (ref "Q2") (pin "2") (pinfunction "S_2") (pintype "passive"))
      (node (ref "R12") (pin "1") (pinfunction "1_1") (pintype "passive"))
      (node (ref "R13") (pin "2") (pinfunction "2_2") (pintype "passive"))
      (node (ref "R14") (pin "1") (pinfunction "1_1") (pintype "passive"))
      (node (ref "U2") (pin "3") (pinfunction "Vout_3") (pintype "passive"))
    )
    (net (code "23") (name "3_6V_1_OUT") (class "Default")
      (node (ref "J2") (pin "18") (pinfunction "18_18") (pintype "passive"))
      (node (ref "J2") (pin "20") (pinfunction "20_20") (pintype "passive"))
      (node (ref "Q2") (pin "3") (pinfunction "D_3") (pintype "passive"))
      (node (ref "R11") (pin "1") (pinfunction "1_1") (pintype "passive"))
      (node (ref "R12") (pin "2") (pinfunction "2_2") (pintype "passive"))
    )
    (net (code "24") (name "3_6V_2") (class "Default")
      (node (ref "C13") (pin "1") (pinfunction "1_1") (pintype "passive"))
      (node (ref "C15") (pin "1") (pinfunction "1_1") (pintype "passive"))
      (node (ref "C16") (pin "1") (pinfunction "1_1") (pintype "passive"))
      (node (ref "Q4") (pin "2") (pinfunction "S_2") (pintype "passive"))
      (node (ref "R20") (pin "1") (pinfunction "1_1") (pintype "passive"))
      (node (ref "R21") (pin "2") (pinfunction "2_2") (pintype "passive"))
      (node (ref "R22") (pin "1") (pinfunction "1_1") (pintype "passive"))
      (node (ref "U5") (pin "3") (pinfunction "Vout_3") (pintype "passive"))
    )
    (net (code "25") (name "3_6V_2_OUT") (class "Default")
      (node (ref "J2") (pin "17") (pinfunction "17_17") (pintype "passive"))
      (node (ref "J2") (pin "19") (pinfunction "19_19") (pintype "passive"))
      (node (ref "Q4") (pin "3") (pinfunction "D_3") (pintype "passive"))
      (node (ref "R19") (pin "1") (pinfunction "1_1") (pintype "passive"))
      (node (ref "R20") (pin "2") (pinfunction "2_2") (pintype "passive"))
    )
    (net (code "26") (name "3_6V_3") (class "Default")
      (node (ref "C19") (pin "1") (pinfunction "1_1") (pintype "passive"))
      (node (ref "C21") (pin "1") (pinfunction "1_1") (pintype "passive"))
      (node (ref "C22") (pin "1") (pinfunction "1_1") (pintype "passive"))
      (node (ref "Q6") (pin "2") (pinfunction "S_2") (pintype "passive"))
      (node (ref "R28") (pin "1") (pinfunction "1_1") (pintype "passive"))
      (node (ref "R29") (pin "2") (pinfunction "2_2") (pintype "passive"))
      (node (ref "R30") (pin "1") (pinfunction "1_1") (pintype "passive"))
      (node (ref "U6") (pin "3") (pinfunction "Vout_3") (pintype "passive"))
    )
    (net (code "27") (name "3_6V_3_OUT") (class "Default")
      (node (ref "J2") (pin "13") (pinfunction "13_13") (pintype "passive"))
      (node (ref "J2") (pin "15") (pinfunction "15_15") (pintype "passive"))
      (node (ref "Q6") (pin "3") (pinfunction "D_3") (pintype "passive"))
      (node (ref "R27") (pin "1") (pinfunction "1_1") (pintype "passive"))
      (node (ref "R28") (pin "2") (pinfunction "2_2") (pintype "passive"))
    )
    (net (code "28") (name "3_6V_4") (class "Default")
      (node (ref "C25") (pin "1") (pinfunction "1_1") (pintype "passive"))
      (node (ref "C27") (pin "1") (pinfunction "1_1") (pintype "passive"))
      (node (ref "C28") (pin "1") (pinfunction "1_1") (pintype "passive"))
      (node (ref "Q8") (pin "2") (pinfunction "S_2") (pintype "passive"))
      (node (ref "R36") (pin "1") (pinfunction "1_1") (pintype "passive"))
      (node (ref "R37") (pin "2") (pinfunction "2_2") (pintype "passive"))
      (node (ref "R38") (pin "1") (pinfunction "1_1") (pintype "passive"))
      (node (ref "U8") (pin "3") (pinfunction "Vout_3") (pintype "passive"))
    )
    (net (code "29") (name "3_6V_4_OUT") (class "Default")
      (node (ref "J2") (pin "11") (pinfunction "11_11") (pintype "passive"))
      (node (ref "J2") (pin "9") (pinfunction "9_9") (pintype "passive"))
      (node (ref "Q8") (pin "3") (pinfunction "D_3") (pintype "passive"))
      (node (ref "R35") (pin "1") (pinfunction "1_1") (pintype "passive"))
      (node (ref "R36") (pin "2") (pinfunction "2_2") (pintype "passive"))
    )
    (net (code "30") (name "3_6V_5") (class "Default")
      (node (ref "C31") (pin "1") (pinfunction "1_1") (pintype "passive"))
      (node (ref "C33") (pin "1") (pinfunction "1_1") (pintype "passive"))
      (node (ref "C34") (pin "1") (pinfunction "1_1") (pintype "passive"))
      (node (ref "Q10") (pin "2") (pinfunction "S_2") (pintype "passive"))
      (node (ref "R44") (pin "1") (pinfunction "1_1") (pintype "passive"))
      (node (ref "R45") (pin "2") (pinfunction "2_2") (pintype "passive"))
      (node (ref "R46") (pin "1") (pinfunction "1_1") (pintype "passive"))
      (node (ref "U11") (pin "3") (pinfunction "Vout_3") (pintype "passive"))
    )
    (net (code "31") (name "3_6V_5_OUT") (class "Default")
      (node (ref "J2") (pin "5") (pinfunction "5_5") (pintype "passive"))
      (node (ref "J2") (pin "7") (pinfunction "7_7") (pintype "passive"))
      (node (ref "Q10") (pin "3") (pinfunction "D_3") (pintype "passive"))
      (node (ref "R43") (pin "1") (pinfunction "1_1") (pintype "passive"))
      (node (ref "R44") (pin "2") (pinfunction "2_2") (pintype "passive"))
    )
    (net (code "32") (name "3_6V_6") (class "Default")
      (node (ref "C37") (pin "1") (pinfunction "1_1") (pintype "passive"))
      (node (ref "C39") (pin "1") (pinfunction "1_1") (pintype "passive"))
      (node (ref "C40") (pin "1") (pinfunction "1_1") (pintype "passive"))
      (node (ref "Q12") (pin "2") (pinfunction "S_2") (pintype "passive"))
      (node (ref "R52") (pin "1") (pinfunction "1_1") (pintype "passive"))
      (node (ref "R53") (pin "2") (pinfunction "2_2") (pintype "passive"))
      (node (ref "R54") (pin "1") (pinfunction "1_1") (pintype "passive"))
      (node (ref "U13") (pin "3") (pinfunction "Vout_3") (pintype "passive"))
    )
    (net (code "33") (name "3_6V_6_OUT") (class "Default")
      (node (ref "J2") (pin "1") (pinfunction "1_1") (pintype "passive"))
      (node (ref "J2") (pin "3") (pinfunction "3_3") (pintype "passive"))
      (node (ref "Q12") (pin "3") (pinfunction "D_3") (pintype "passive"))
      (node (ref "R51") (pin "1") (pinfunction "1_1") (pintype "passive"))
      (node (ref "R52") (pin "2") (pinfunction "2_2") (pintype "passive"))
    )
    (net (code "34") (name "5V") (class "Default")
      (node (ref "C14") (pin "1") (pinfunction "1_1") (pintype "passive"))
      (node (ref "C20") (pin "1") (pinfunction "1_1") (pintype "passive"))
      (node (ref "C26") (pin "1") (pinfunction "1_1") (pintype "passive"))
      (node (ref "C32") (pin "1") (pinfunction "1_1") (pintype "passive"))
      (node (ref "C38") (pin "1") (pinfunction "1_1") (pintype "passive"))
      (node (ref "C49") (pin "1") (pinfunction "1_1") (pintype "passive"))
      (node (ref "C8") (pin "1") (pinfunction "1_1") (pintype "passive"))
      (node (ref "L2") (pin "2") (pinfunction "2_2") (pintype "passive"))
      (node (ref "R56") (pin "2") (pinfunction "2_2") (pintype "passive"))
      (node (ref "R62") (pin "2") (pinfunction "2_2") (pintype "passive"))
      (node (ref "U11") (pin "2") (pinfunction "Vin_2") (pintype "passive"))
      (node (ref "U13") (pin "2") (pinfunction "Vin_2") (pintype "passive"))
      (node (ref "U2") (pin "2") (pinfunction "Vin_2") (pintype "passive"))
      (node (ref "U5") (pin "2") (pinfunction "Vin_2") (pintype "passive"))
      (node (ref "U6") (pin "2") (pinfunction "Vin_2") (pintype "passive"))
      (node (ref "U8") (pin "2") (pinfunction "Vin_2") (pintype "passive"))
    )
    (net (code "35") (name "GND") (class "Default")
      (node (ref "C10") (pin "2") (pinfunction "2_2") (pintype "passive"))
      (node (ref "C12") (pin "1") (pinfunction "1_1") (pintype "passive"))
      (node (ref "C13") (pin "2") (pinfunction "2_2") (pintype "passive"))
      (node (ref "C14") (pin "2") (pinfunction "2_2") (pintype "passive"))
      (node (ref "C15") (pin "2") (pinfunction "2_2") (pintype "passive"))
      (node (ref "C16") (pin "2") (pinfunction "2_2") (pintype "passive"))
      (node (ref "C18") (pin "1") (pinfunction "1_1") (pintype "passive"))
      (node (ref "C19") (pin "2") (pinfunction "2_2") (pintype "passive"))
      (node (ref "C20") (pin "2") (pinfunction "2_2") (pintype "passive"))
      (node (ref "C21") (pin "2") (pinfunction "2_2") (pintype "passive"))
      (node (ref "C22") (pin "2") (pinfunction "2_2") (pintype "passive"))
      (node (ref "C24") (pin "1") (pinfunction "1_1") (pintype "passive"))
      (node (ref "C25") (pin "2") (pinfunction "2_2") (pintype "passive"))
      (node (ref "C26") (pin "2") (pinfunction "2_2") (pintype "passive"))
      (node (ref "C27") (pin "2") (pinfunction "2_2") (pintype "passive"))
      (node (ref "C28") (pin "2") (pinfunction "2_2") (pintype "passive"))
      (node (ref "C30") (pin "1") (pinfunction "1_1") (pintype "passive"))
      (node (ref "C31") (pin "2") (pinfunction "2_2") (pintype "passive"))
      (node (ref "C32") (pin "2") (pinfunction "2_2") (pintype "passive"))
      (node (ref "C33") (pin "2") (pinfunction "2_2") (pintype "passive"))
      (node (ref "C34") (pin "2") (pinfunction "2_2") (pintype "passive"))
      (node (ref "C36") (pin "1") (pinfunction "1_1") (pintype "passive"))
      (node (ref "C37") (pin "2") (pinfunction "2_2") (pintype "passive"))
      (node (ref "C38") (pin "2") (pinfunction "2_2") (pintype "passive"))
      (node (ref "C39") (pin "2") (pinfunction "2_2") (pintype "passive"))
      (node (ref "C40") (pin "2") (pinfunction "2_2") (pintype "passive"))
      (node (ref "C44") (pin "2") (pinfunction "2_2") (pintype "passive"))
      (node (ref "C45") (pin "2") (pinfunction "2_2") (pintype "passive"))
      (node (ref "C46") (pin "2") (pinfunction "2_2") (pintype "passive"))
      (node (ref "C47") (pin "2") (pinfunction "2_2") (pintype "passive"))
      (node (ref "C48") (pin "2") (pinfunction "2_2") (pintype "passive"))
      (node (ref "C49") (pin "2") (pinfunction "2_2") (pintype "passive"))
      (node (ref "C50") (pin "2") (pinfunction "2_2") (pintype "passive"))
      (node (ref "C51") (pin "2") (pinfunction "2_2") (pintype "passive"))
      (node (ref "C52") (pin "2") (pinfunction "2_2") (pintype "passive"))
      (node (ref "C53") (pin "2") (pinfunction "2_2") (pintype "passive"))
      (node (ref "C6") (pin "1") (pinfunction "1_1") (pintype "passive"))
      (node (ref "C7") (pin "2") (pinfunction "2_2") (pintype "passive"))
      (node (ref "C8") (pin "2") (pinfunction "2_2") (pintype "passive"))
      (node (ref "C9") (pin "2") (pinfunction "2_2") (pintype "passive"))
      (node (ref "D2") (pin "1") (pinfunction "1_1") (pintype "passive"))
      (node (ref "D3") (pin "1") (pinfunction "1_1") (pintype "passive"))
      (node (ref "J2") (pin "10") (pinfunction "10_10") (pintype "passive"))
      (node (ref "J2") (pin "12") (pinfunction "12_12") (pintype "passive"))
      (node (ref "J2") (pin "14") (pinfunction "14_14") (pintype "passive"))
      (node (ref "J2") (pin "16") (pinfunction "16_16") (pintype "passive"))
      (node (ref "J2") (pin "2") (pinfunction "2_2") (pintype "passive"))
      (node (ref "J2") (pin "4") (pinfunction "4_4") (pintype "passive"))
      (node (ref "J2") (pin "6") (pinfunction "6_6") (pintype "passive"))
      (node (ref "J2") (pin "8") (pinfunction "8_8") (pintype "passive"))
      (node (ref "JP1") (pin "2") (pinfunction "2_2") (pintype "passive"))
      (node (ref "JP2") (pin "2") (pinfunction "2_2") (pintype "passive"))
      (node (ref "Q1") (pin "2") (pinfunction "E_2") (pintype "passive"))
      (node (ref "Q11") (pin "2") (pinfunction "E_2") (pintype "passive"))
      (node (ref "Q3") (pin "2") (pinfunction "E_2") (pintype "passive"))
      (node (ref "Q5") (pin "2") (pinfunction "E_2") (pintype "passive"))
      (node (ref "Q7") (pin "2") (pinfunction "E_2") (pintype "passive"))
      (node (ref "Q9") (pin "2") (pinfunction "E_2") (pintype "passive"))
      (node (ref "R57") (pin "1") (pinfunction "1_1") (pintype "passive"))
      (node (ref "R60") (pin "1") (pinfunction "1_1") (pintype "passive"))
      (node (ref "R63") (pin "1") (pinfunction "1_1") (pintype "passive"))
      (node (ref "R64") (pin "1") (pinfunction "1_1") (pintype "passive"))
      (node (ref "U10") (pin "1") (pinfunction "A1_1") (pintype "passive"))
      (node (ref "U10") (pin "2") (pinfunction "A0_2") (pintype "passive"))
      (node (ref "U10") (pin "6") (pinfunction "GND_6") (pintype "passive"))
      (node (ref "U11") (pin "1") (pinfunction "GND_1") (pintype "passive"))
      (node (ref "U12") (pin "1") (pinfunction "A1_1") (pintype "passive"))
      (node (ref "U12") (pin "2") (pinfunction "A0_2") (pintype "passive"))
      (node (ref "U12") (pin "6") (pinfunction "GND_6") (pintype "passive"))
      (node (ref "U13") (pin "1") (pinfunction "GND_1") (pintype "passive"))
      (node (ref "U14") (pin "6") (pinfunction "GND_6") (pintype "passive"))
      (node (ref "U14") (pin "9") (pinfunction "PAD_9") (pintype "passive"))
      (node (ref "U15") (pin "6") (pinfunction "GND_6") (pintype "passive"))
      (node (ref "U15") (pin "9") (pinfunction "PAD_9") (pintype "passive"))
      (node (ref "U16") (pin "1") (pinfunction "GND_1") (pintype "passive"))
      (node (ref "U2") (pin "1") (pinfunction "GND_1") (pintype "passive"))
      (node (ref "U3") (pin "1") (pinfunction "A1_1") (pintype "passive"))
      (node (ref "U3") (pin "2") (pinfunction "A0_2") (pintype "passive"))
      (node (ref "U3") (pin "6") (pinfunction "GND_6") (pintype "passive"))
      (node (ref "U4") (pin "1") (pinfunction "A1_1") (pintype "passive"))
      (node (ref "U4") (pin "2") (pinfunction "A0_2") (pintype "passive"))
      (node (ref "U4") (pin "6") (pinfunction "GND_6") (pintype "passive"))
      (node (ref "U5") (pin "1") (pinfunction "GND_1") (pintype "passive"))
      (node (ref "U6") (pin "1") (pinfunction "GND_1") (pintype "passive"))
      (node (ref "U7") (pin "1") (pinfunction "A1_1") (pintype "passive"))
      (node (ref "U7") (pin "2") (pinfunction "A0_2") (pintype "passive"))
      (node (ref "U7") (pin "6") (pinfunction "GND_6") (pintype "passive"))
      (node (ref "U8") (pin "1") (pinfunction "GND_1") (pintype "passive"))
      (node (ref "U9") (pin "1") (pinfunction "A1_1") (pintype "passive"))
      (node (ref "U9") (pin "2") (pinfunction "A0_2") (pintype "passive"))
      (node (ref "U9") (pin "6") (pinfunction "GND_6") (pintype "passive"))
    )
    (net (code "36") (name "Net-(Q1-B)") (class "Default")
      (node (ref "Q1") (pin "1") (pinfunction "B_1") (pintype "passive"))
      (node (ref "R10") (pin "1") (pinfunction "1_1") (pintype "passive"))
    )
    (net (code "37") (name "Net-(Q1-C)") (class "Default")
      (node (ref "Q1") (pin "3") (pinfunction "C_3") (pintype "passive"))
      (node (ref "R9") (pin "2") (pinfunction "2_2") (pintype "passive"))
    )
    (net (code "38") (name "Net-(Q2-G)") (class "Default")
      (node (ref "Q2") (pin "1") (pinfunction "G_1") (pintype "passive"))
      (node (ref "R13") (pin "1") (pinfunction "1_1") (pintype "passive"))
      (node (ref "R9") (pin "1") (pinfunction "1_1") (pintype "passive"))
    )
    (net (code "39") (name "Net-(Q3-B)") (class "Default")
      (node (ref "Q3") (pin "1") (pinfunction "B_1") (pintype "passive"))
      (node (ref "R18") (pin "1") (pinfunction "1_1") (pintype "passive"))
    )
    (net (code "40") (name "Net-(Q3-C)") (class "Default")
      (node (ref "Q3") (pin "3") (pinfunction "C_3") (pintype "passive"))
      (node (ref "R17") (pin "2") (pinfunction "2_2") (pintype "passive"))
    )
    (net (code "41") (name "Net-(Q4-G)") (class "Default")
      (node (ref "Q4") (pin "1") (pinfunction "G_1") (pintype "passive"))
      (node (ref "R17") (pin "1") (pinfunction "1_1") (pintype "passive"))
      (node (ref "R21") (pin "1") (pinfunction "1_1") (pintype "passive"))
    )
    (net (code "42") (name "Net-(Q5-B)") (class "Default")
      (node (ref "Q5") (pin "1") (pinfunction "B_1") (pintype "passive"))
      (node (ref "R26") (pin "1") (pinfunction "1_1") (pintype "passive"))
    )
    (net (code "43") (name "Net-(Q5-C)") (class "Default")
      (node (ref "Q5") (pin "3") (pinfunction "C_3") (pintype "passive"))
      (node (ref "R25") (pin "2") (pinfunction "2_2") (pintype "passive"))
    )
    (net (code "44") (name "Net-(Q6-G)") (class "Default")
      (node (ref "Q6") (pin "1") (pinfunction "G_1") (pintype "passive"))
      (node (ref "R25") (pin "1") (pinfunction "1_1") (pintype "passive"))
      (node (ref "R29") (pin "1") (pinfunction "1_1") (pintype "passive"))
    )
    (net (code "45") (name "Net-(Q7-B)") (class "Default")
      (node (ref "Q7") (pin "1") (pinfunction "B_1") (pintype "passive"))
      (node (ref "R34") (pin "1") (pinfunction "1_1") (pintype "passive"))
    )
    (net (code "46") (name "Net-(Q7-C)") (class "Default")
      (node (ref "Q7") (pin "3") (pinfunction "C_3") (pintype "passive"))
      (node (ref "R33") (pin "2") (pinfunction "2_2") (pintype "passive"))
    )
    (net (code "47") (name "Net-(Q8-G)") (class "Default")
      (node (ref "Q8") (pin "1") (pinfunction "G_1") (pintype "passive"))
      (node (ref "R33") (pin "1") (pinfunction "1_1") (pintype "passive"))
      (node (ref "R37") (pin "1") (pinfunction "1_1") (pintype "passive"))
    )
    (net (code "48") (name "Net-(Q9-B)") (class "Default")
      (node (ref "Q9") (pin "1") (pinfunction "B_1") (pintype "passive"))
      (node (ref "R42") (pin "1") (pinfunction "1_1") (pintype "passive"))
    )
    (net (code "49") (name "Net-(Q9-C)") (class "Default")
      (node (ref "Q9") (pin "3") (pinfunction "C_3") (pintype "passive"))
      (node (ref "R41") (pin "2") (pinfunction "2_2") (pintype "passive"))
    )
    (net (code "50") (name "Net-(Q10-G)") (class "Default")
      (node (ref "Q10") (pin "1") (pinfunction "G_1") (pintype "passive"))
      (node (ref "R41") (pin "1") (pinfunction "1_1") (pintype "passive"))
      (node (ref "R45") (pin "1") (pinfunction "1_1") (pintype "passive"))
    )
    (net (code "51") (name "Net-(Q11-B)") (class "Default")
      (node (ref "Q11") (pin "1") (pinfunction "B_1") (pintype "passive"))
      (node (ref "R50") (pin "1") (pinfunction "1_1") (pintype "passive"))
    )
    (net (code "52") (name "Net-(Q11-C)") (class "Default")
      (node (ref "Q11") (pin "3") (pinfunction "C_3") (pintype "passive"))
      (node (ref "R49") (pin "2") (pinfunction "2_2") (pintype "passive"))
    )
    (net (code "53") (name "Net-(Q12-G)") (class "Default")
      (node (ref "Q12") (pin "1") (pinfunction "G_1") (pintype "passive"))
      (node (ref "R49") (pin "1") (pinfunction "1_1") (pintype "passive"))
      (node (ref "R53") (pin "1") (pinfunction "1_1") (pintype "passive"))
    )
    (net (code "54") (name "Net-(R57-Pad2)") (class "Default")
      (node (ref "R57") (pin "2") (pinfunction "2_2") (pintype "passive"))
      (node (ref "R58") (pin "1") (pinfunction "1_1") (pintype "passive"))
    )
    (net (code "55") (name "Net-(R60-Pad2)") (class "Default")
      (node (ref "R60") (pin "2") (pinfunction "2_2") (pintype "passive"))
      (node (ref "R61") (pin "1") (pinfunction "1_1") (pintype "passive"))
    )
    (net (code "56") (name "Net-(U3-Vin+)") (class "Default")
      (node (ref "C11") (pin "2") (pinfunction "2_2") (pintype "passive"))
      (node (ref "R14") (pin "2") (pinfunction "2_2") (pintype "passive"))
      (node (ref "U3") (pin "8") (pinfunction "Vin+_8") (pintype "passive"))
    )
    (net (code "57") (name "Net-(U3-Vin-)") (class "Default")
      (node (ref "C11") (pin "1") (pinfunction "1_1") (pintype "passive"))
      (node (ref "R11") (pin "2") (pinfunction "2_2") (pintype "passive"))
      (node (ref "U3") (pin "7") (pinfunction "Vin-_7") (pintype "passive"))
    )
    (net (code "58") (name "Net-(U4-Vin+)") (class "Default")
      (node (ref "C17") (pin "2") (pinfunction "2_2") (pintype "passive"))
      (node (ref "R22") (pin "2") (pinfunction "2_2") (pintype "passive"))
      (node (ref "U4") (pin "8") (pinfunction "Vin+_8") (pintype "passive"))
    )
    (net (code "59") (name "Net-(U4-Vin-)") (class "Default")
      (node (ref "C17") (pin "1") (pinfunction "1_1") (pintype "passive"))
      (node (ref "R19") (pin "2") (pinfunction "2_2") (pintype "passive"))
      (node (ref "U4") (pin "7") (pinfunction "Vin-_7") (pintype "passive"))
    )
    (net (code "60") (name "Net-(U7-Vin+)") (class "Default")
      (node (ref "C23") (pin "2") (pinfunction "2_2") (pintype "passive"))
      (node (ref "R30") (pin "2") (pinfunction "2_2") (pintype "passive"))
      (node (ref "U7") (pin "8") (pinfunction "Vin+_8") (pintype "passive"))
    )
    (net (code "61") (name "Net-(U7-Vin-)") (class "Default")
      (node (ref "C23") (pin "1") (pinfunction "1_1") (pintype "passive"))
      (node (ref "R27") (pin "2") (pinfunction "2_2") (pintype "passive"))
      (node (ref "U7") (pin "7") (pinfunction "Vin-_7") (pintype "passive"))
    )
    (net (code "62") (name "Net-(U9-Vin+)") (class "Default")
      (node (ref "C29") (pin "2") (pinfunction "2_2") (pintype "passive"))
      (node (ref "R38") (pin "2") (pinfunction "2_2") (pintype "passive"))
      (node (ref "U9") (pin "8") (pinfunction "Vin+_8") (pintype "passive"))
    )
    (net (code "63") (name "Net-(U9-Vin-)") (class "Default")
      (node (ref "C29") (pin "1") (pinfunction "1_1") (pintype "passive"))
      (node (ref "R35") (pin "2") (pinfunction "2_2") (pintype "passive"))
      (node (ref "U9") (pin "7") (pinfunction "Vin-_7") (pintype "passive"))
    )
    (net (code "64") (name "Net-(U10-Vin+)") (class "Default")
      (node (ref "C35") (pin "2") (pinfunction "2_2") (pintype "passive"))
      (node (ref "R46") (pin "2") (pinfunction "2_2") (pintype "passive"))
      (node (ref "U10") (pin "8") (pinfunction "Vin+_8") (pintype "passive"))
    )
    (net (code "65") (name "Net-(U10-Vin-)") (class "Default")
      (node (ref "C35") (pin "1") (pinfunction "1_1") (pintype "passive"))
      (node (ref "R43") (pin "2") (pinfunction "2_2") (pintype "passive"))
      (node (ref "U10") (pin "7") (pinfunction "Vin-_7") (pintype "passive"))
    )
    (net (code "66") (name "Net-(U12-Vin+)") (class "Default")
      (node (ref "C41") (pin "2") (pinfunction "2_2") (pintype "passive"))
      (node (ref "R54") (pin "2") (pinfunction "2_2") (pintype "passive"))
      (node (ref "U12") (pin "8") (pinfunction "Vin+_8") (pintype "passive"))
    )
    (net (code "67") (name "Net-(U12-Vin-)") (class "Default")
      (node (ref "C41") (pin "1") (pinfunction "1_1") (pintype "passive"))
      (node (ref "R51") (pin "2") (pinfunction "2_2") (pintype "passive"))
      (node (ref "U12") (pin "7") (pinfunction "Vin-_7") (pintype "passive"))
    )
    (net (code "68") (name "Net-(U14-BOOT)") (class "Default")
      (node (ref "C42") (pin "2") (pinfunction "2_2") (pintype "passive"))
      (node (ref "U14") (pin "1") (pinfunction "BOOT_1") (pintype "passive"))
    )
    (net (code "69") (name "Net-(U14-PH)") (class "Default")
      (node (ref "C42") (pin "1") (pinfunction "1_1") (pintype "passive"))
      (node (ref "D2") (pin "2") (pinfunction "2_2") (pintype "passive"))
      (node (ref "L1") (pin "1") (pinfunction "1_1") (pintype "passive"))
      (node (ref "U14") (pin "8") (pinfunction "PH_8") (pintype "passive"))
    )
    (net (code "70") (name "Net-(U14-VSNS)") (class "Default")
      (node (ref "R58") (pin "2") (pinfunction "2_2") (pintype "passive"))
      (node (ref "R59") (pin "1") (pinfunction "1_1") (pintype "passive"))
      (node (ref "U14") (pin "4") (pinfunction "VSNS_4") (pintype "passive"))
    )
    (net (code "71") (name "Net-(U15-BOOT)") (class "Default")
      (node (ref "C43") (pin "2") (pinfunction "2_2") (pintype "passive"))
      (node (ref "U15") (pin "1") (pinfunction "BOOT_1") (pintype "passive"))
    )
    (net (code "72") (name "Net-(U15-PH)") (class "Default")
      (node (ref "C43") (pin "1") (pinfunction "1_1") (pintype "passive"))
      (node (ref "D3") (pin "2") (pinfunction "2_2") (pintype "passive"))
      (node (ref "L2") (pin "1") (pinfunction "1_1") (pintype "passive"))
      (node (ref "U15") (pin "8") (pinfunction "PH_8") (pintype "passive"))
    )
    (net (code "73") (name "Net-(U15-VSNS)") (class "Default")
      (node (ref "R61") (pin "2") (pinfunction "2_2") (pintype "passive"))
      (node (ref "R62") (pin "1") (pinfunction "1_1") (pintype "passive"))
      (node (ref "U15") (pin "4") (pinfunction "VSNS_4") (pintype "passive"))
    )
    (net (code "74") (name "VIN_5V") (class "Default")
      (node (ref "C48") (pin "1") (pinfunction "1_1") (pintype "passive"))
      (node (ref "C51") (pin "1") (pinfunction "1_1") (pintype "passive"))
      (node (ref "L1") (pin "2") (pinfunction "2_2") (pintype "passive"))
      (node (ref "R55") (pin "2") (pinfunction "2_2") (pintype "passive"))
      (node (ref "R59") (pin "2") (pinfunction "2_2") (pintype "passive"))
      (node (ref "U16") (pin "2") (pinfunction "Vin_2") (pintype "passive"))
    )
    (net (code "75") (name "VIN_12V") (class "Default")
      (node (ref "C44") (pin "1") (pinfunction "1_1") (pintype "passive"))
      (node (ref "C45") (pin "1") (pinfunction "1_1") (pintype "passive"))
      (node (ref "C46") (pin "1") (pinfunction "1_1") (pintype "passive"))
      (node (ref "C47") (pin "1") (pinfunction "1_1") (pintype "passive"))
      (node (ref "JP1") (pin "1") (pinfunction "1_1") (pintype "passive"))
      (node (ref "JP2") (pin "1") (pinfunction "1_1") (pintype "passive"))
      (node (ref "U14") (pin "7") (pinfunction "VIN_7") (pintype "passive"))
      (node (ref "U15") (pin "7") (pinfunction "VIN_7") (pintype "passive"))
    )
    (net (code "76") (name "unconnected-(U14-ENA-Pad5)") (class "Default")
      (node (ref "U14") (pin "5") (pinfunction "ENA_5") (pintype "passive"))
    )
    (net (code "77") (name "unconnected-(U14-NC-Pad2)") (class "Default")
      (node (ref "U14") (pin "2") (pinfunction "NC_2") (pintype "passive"))
    )
    (net (code "78") (name "unconnected-(U14-NC-Pad3)") (class "Default")
      (node (ref "U14") (pin "3") (pinfunction "NC_3") (pintype "passive"))
    )
    (net (code "79") (name "unconnected-(U15-ENA-Pad5)") (class "Default")
      (node (ref "U15") (pin "5") (pinfunction "ENA_5") (pintype "passive"))
    )
    (net (code "80") (name "unconnected-(U15-NC-Pad2)") (class "Default")
      (node (ref "U15") (pin "2") (pinfunction "NC_2") (pintype "passive"))
    )
    (net (code "81") (name "unconnected-(U15-NC-Pad3)") (class "Default")
      (node (ref "U15") (pin "3") (pinfunction "NC_3") (pintype "passive"))
    )
  )
)
